# TSOL_102A.net
KiCad netlist of a schematic drawn in EAGLE
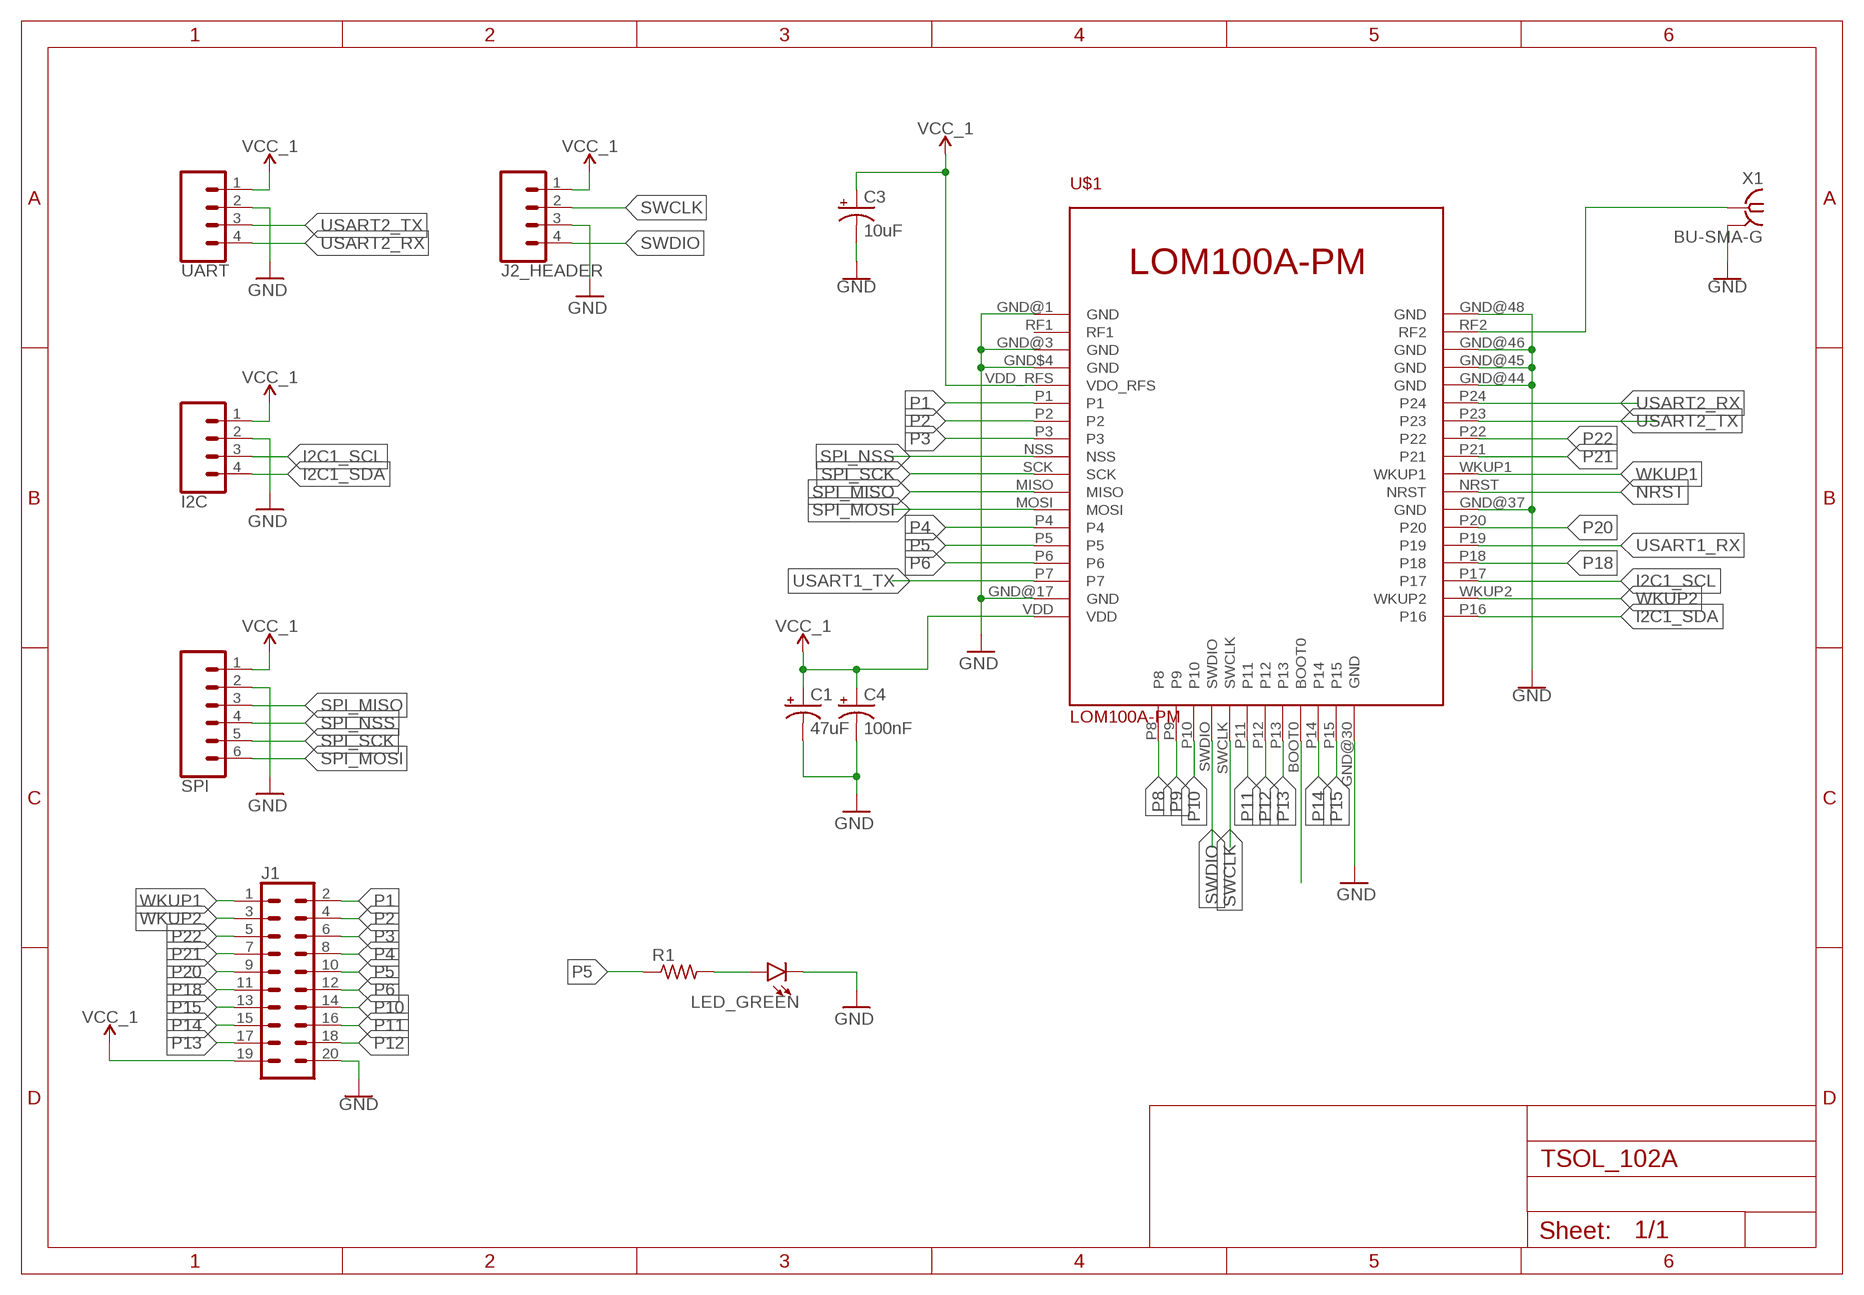
[diagram p0: schematic, sheet 1]

(export (version "E")
  (design (tool "Eeschema 10.0.6"))
  (components
    (comp (ref "C1")
      (value "47uF")
      (footprint "eagle-import:CPOL-RADIAL-5MM-10MM-KIT")
      (libsource (lib "eagle-import") (part "1000UF-RADIAL-5MM-35V-20%-KIT"))
    )
    (comp (ref "C3")
      (value "10uF")
      (footprint "eagle-import:CPOL-RADIAL-5MM-10MM-KIT")
      (libsource (lib "eagle-import") (part "1000UF-RADIAL-5MM-35V-20%-KIT"))
    )
    (comp (ref "C4")
      (value "100nF")
      (footprint "eagle-import:CPOL-RADIAL-5MM-10MM-KIT")
      (libsource (lib "eagle-import") (part "1000UF-RADIAL-5MM-35V-20%-KIT"))
    )
    (comp (ref "I2C")
      (value "CONN_04LONGPADS")
      (footprint "eagle-import:1X04_LONGPADS")
      (libsource (lib "eagle-import") (part "CONN_04LONGPADS"))
    )
    (comp (ref "J1")
      (value "CONN_10X2")
      (footprint "eagle-import:2X10")
      (libsource (lib "eagle-import") (part "CONN_10X2"))
    )
    (comp (ref "J2_HEADER")
      (value "CONN_04LONGPADS")
      (footprint "eagle-import:1X04_LONGPADS")
      (libsource (lib "eagle-import") (part "CONN_04LONGPADS"))
    )
    (comp (ref "LED_GREEN")
      (value "LED5MM")
      (footprint "eagle-import:LED_5MM")
      (libsource (lib "eagle-import") (part "LED5MM"))
    )
    (comp (ref "R1")
      (value "R-US_0204/7")
      (footprint "eagle-import:0204_7")
      (libsource (lib "eagle-import") (part "R-US_0204/7"))
    )
    (comp (ref "SPI")
      (value "CONN_06LONGPADS")
      (footprint "eagle-import:1X06_LONGPADS")
      (libsource (lib "eagle-import") (part "CONN_06LONGPADS"))
    )
    (comp (ref "U$1")
      (value "LOM100A-PM")
      (footprint "eagle-import:LOM100A-PM")
      (libsource (lib "eagle-import") (part "LOM100A-PM"))
    )
    (comp (ref "UART")
      (value "CONN_04LONGPADS")
      (footprint "eagle-import:1X04_LONGPADS")
      (libsource (lib "eagle-import") (part "CONN_04LONGPADS"))
    )
    (comp (ref "X1")
      (value "BU-SMA-G")
      (footprint "eagle-import:BU-SMA-G")
      (libsource (lib "eagle-import") (part "BU-SMA-G"))
    )
  )
  (nets
    (net (code "1") (name "GND") (class "Default")
      (node (ref "C1") (pin "-") (pinfunction "-_-") (pintype "passive"))
      (node (ref "C3") (pin "-") (pinfunction "-_-") (pintype "passive"))
      (node (ref "C4") (pin "-") (pinfunction "-_-") (pintype "passive"))
      (node (ref "I2C") (pin "2") (pinfunction "2_2") (pintype "passive"))
      (node (ref "J1") (pin "20") (pinfunction "20_20") (pintype "passive"))
      (node (ref "J2_HEADER") (pin "3") (pinfunction "3_3") (pintype "passive"))
      (node (ref "LED_GREEN") (pin "K") (pinfunction "C_K") (pintype "passive"))
      (node (ref "SPI") (pin "2") (pinfunction "2_2") (pintype "passive"))
      (node (ref "U$1") (pin "GND$4") (pinfunction "GND_GND$4") (pintype "passive"))
      (node (ref "U$1") (pin "GND@1") (pinfunction "GND_GND@1") (pintype "passive"))
      (node (ref "U$1") (pin "GND@17") (pinfunction "GND_GND@17") (pintype "passive"))
      (node (ref "U$1") (pin "GND@3") (pinfunction "GND_GND@3") (pintype "passive"))
      (node (ref "U$1") (pin "GND@30") (pinfunction "GND_GND@30") (pintype "passive"))
      (node (ref "U$1") (pin "GND@37") (pinfunction "GND_GND@37") (pintype "passive"))
      (node (ref "U$1") (pin "GND@44") (pinfunction "GND_GND@44") (pintype "passive"))
      (node (ref "U$1") (pin "GND@45") (pinfunction "GND_GND@45") (pintype "passive"))
      (node (ref "U$1") (pin "GND@46") (pinfunction "GND_GND@46") (pintype "passive"))
      (node (ref "U$1") (pin "GND@48") (pinfunction "GND_GND@48") (pintype "passive"))
      (node (ref "UART") (pin "2") (pinfunction "2_2") (pintype "passive"))
      (node (ref "X1") (pin "2") (pinfunction "2_2") (pintype "passive"))
      (node (ref "X1") (pin "3") (pinfunction "2_3") (pintype "passive"))
      (node (ref "X1") (pin "4") (pinfunction "2_4") (pintype "passive"))
      (node (ref "X1") (pin "5") (pinfunction "2_5") (pintype "passive"))
    )
    (net (code "2") (name "I2C1_SCL") (class "Default")
      (node (ref "I2C") (pin "3") (pinfunction "3_3") (pintype "passive"))
      (node (ref "U$1") (pin "P17") (pinfunction "P17_P17") (pintype "passive"))
    )
    (net (code "3") (name "I2C1_SDA") (class "Default")
      (node (ref "I2C") (pin "4") (pinfunction "4_4") (pintype "passive"))
      (node (ref "U$1") (pin "P16") (pinfunction "P16_P16") (pintype "passive"))
    )
    (net (code "4") (name "NRST") (class "Default")
      (node (ref "U$1") (pin "NRST") (pinfunction "NRST_NRST") (pintype "passive"))
    )
    (net (code "5") (name "Net-(LED_GREEN-PadA)") (class "Default")
      (node (ref "LED_GREEN") (pin "A") (pinfunction "A_A") (pintype "passive"))
      (node (ref "R1") (pin "2") (pinfunction "2_2") (pintype "passive"))
    )
    (net (code "6") (name "Net-(U$1-PadRF2)") (class "Default")
      (node (ref "U$1") (pin "RF2") (pinfunction "RF2_RF2") (pintype "passive"))
      (node (ref "X1") (pin "1") (pinfunction "1_1") (pintype "passive"))
    )
    (net (code "7") (name "P1") (class "Default")
      (node (ref "J1") (pin "2") (pinfunction "2_2") (pintype "passive"))
      (node (ref "U$1") (pin "P1") (pinfunction "P1_P1") (pintype "passive"))
    )
    (net (code "8") (name "P2") (class "Default")
      (node (ref "J1") (pin "4") (pinfunction "4_4") (pintype "passive"))
      (node (ref "U$1") (pin "P2") (pinfunction "P2_P2") (pintype "passive"))
    )
    (net (code "9") (name "P3") (class "Default")
      (node (ref "J1") (pin "6") (pinfunction "6_6") (pintype "passive"))
      (node (ref "U$1") (pin "P3") (pinfunction "P3_P3") (pintype "passive"))
    )
    (net (code "10") (name "P4") (class "Default")
      (node (ref "J1") (pin "8") (pinfunction "8_8") (pintype "passive"))
      (node (ref "U$1") (pin "P4") (pinfunction "P4_P4") (pintype "passive"))
    )
    (net (code "11") (name "P5") (class "Default")
      (node (ref "J1") (pin "10") (pinfunction "10_10") (pintype "passive"))
      (node (ref "R1") (pin "1") (pinfunction "1_1") (pintype "passive"))
      (node (ref "U$1") (pin "P5") (pinfunction "P5_P5") (pintype "passive"))
    )
    (net (code "12") (name "P6") (class "Default")
      (node (ref "J1") (pin "12") (pinfunction "12_12") (pintype "passive"))
      (node (ref "U$1") (pin "P6") (pinfunction "P6_P6") (pintype "passive"))
    )
    (net (code "13") (name "P8") (class "Default")
      (node (ref "U$1") (pin "P8") (pinfunction "P8_P8") (pintype "passive"))
    )
    (net (code "14") (name "P9") (class "Default")
      (node (ref "U$1") (pin "P9") (pinfunction "P9_P9") (pintype "passive"))
    )
    (net (code "15") (name "P10") (class "Default")
      (node (ref "J1") (pin "14") (pinfunction "14_14") (pintype "passive"))
      (node (ref "U$1") (pin "P10") (pinfunction "P10_P10") (pintype "passive"))
    )
    (net (code "16") (name "P11") (class "Default")
      (node (ref "J1") (pin "16") (pinfunction "16_16") (pintype "passive"))
      (node (ref "U$1") (pin "P11") (pinfunction "P11_P11") (pintype "passive"))
    )
    (net (code "17") (name "P12") (class "Default")
      (node (ref "J1") (pin "18") (pinfunction "18_18") (pintype "passive"))
      (node (ref "U$1") (pin "P12") (pinfunction "P12_P12") (pintype "passive"))
    )
    (net (code "18") (name "P13") (class "Default")
      (node (ref "J1") (pin "17") (pinfunction "17_17") (pintype "passive"))
      (node (ref "U$1") (pin "P13") (pinfunction "P13_P13") (pintype "passive"))
    )
    (net (code "19") (name "P14") (class "Default")
      (node (ref "J1") (pin "15") (pinfunction "15_15") (pintype "passive"))
      (node (ref "U$1") (pin "P14") (pinfunction "P14_P14") (pintype "passive"))
    )
    (net (code "20") (name "P15") (class "Default")
      (node (ref "J1") (pin "13") (pinfunction "13_13") (pintype "passive"))
      (node (ref "U$1") (pin "P15") (pinfunction "P15_P15") (pintype "passive"))
    )
    (net (code "21") (name "P18") (class "Default")
      (node (ref "J1") (pin "11") (pinfunction "11_11") (pintype "passive"))
      (node (ref "U$1") (pin "P18") (pinfunction "P18_P18") (pintype "passive"))
    )
    (net (code "22") (name "P20") (class "Default")
      (node (ref "J1") (pin "9") (pinfunction "9_9") (pintype "passive"))
      (node (ref "U$1") (pin "P20") (pinfunction "P20_P20") (pintype "passive"))
    )
    (net (code "23") (name "P21") (class "Default")
      (node (ref "J1") (pin "7") (pinfunction "7_7") (pintype "passive"))
      (node (ref "U$1") (pin "P21") (pinfunction "P21_P21") (pintype "passive"))
    )
    (net (code "24") (name "P22") (class "Default")
      (node (ref "J1") (pin "5") (pinfunction "5_5") (pintype "passive"))
      (node (ref "U$1") (pin "P22") (pinfunction "P22_P22") (pintype "passive"))
    )
    (net (code "25") (name "SPI_MISO") (class "Default")
      (node (ref "SPI") (pin "3") (pinfunction "3_3") (pintype "passive"))
      (node (ref "U$1") (pin "MISO") (pinfunction "MISO_MISO") (pintype "passive"))
    )
    (net (code "26") (name "SPI_MOSI") (class "Default")
      (node (ref "SPI") (pin "6") (pinfunction "6_6") (pintype "passive"))
      (node (ref "U$1") (pin "MOSI") (pinfunction "MOSI_MOSI") (pintype "passive"))
    )
    (net (code "27") (name "SPI_NSS") (class "Default")
      (node (ref "SPI") (pin "4") (pinfunction "4_4") (pintype "passive"))
      (node (ref "U$1") (pin "NSS") (pinfunction "NSS_NSS") (pintype "passive"))
    )
    (net (code "28") (name "SPI_SCK") (class "Default")
      (node (ref "SPI") (pin "5") (pinfunction "5_5") (pintype "passive"))
      (node (ref "U$1") (pin "SCK") (pinfunction "SCK_SCK") (pintype "passive"))
    )
    (net (code "29") (name "SWCLK") (class "Default")
      (node (ref "J2_HEADER") (pin "2") (pinfunction "2_2") (pintype "passive"))
      (node (ref "U$1") (pin "SWCLK") (pinfunction "SWCLK_SWCLK") (pintype "passive"))
    )
    (net (code "30") (name "SWDIO") (class "Default")
      (node (ref "J2_HEADER") (pin "4") (pinfunction "4_4") (pintype "passive"))
      (node (ref "U$1") (pin "SWDIO") (pinfunction "SWDIO_SWDIO") (pintype "passive"))
    )
    (net (code "31") (name "USART1_RX") (class "Default")
      (node (ref "U$1") (pin "P19") (pinfunction "P19_P19") (pintype "passive"))
    )
    (net (code "32") (name "USART1_TX") (class "Default")
      (node (ref "U$1") (pin "P7") (pinfunction "P7_P7") (pintype "passive"))
    )
    (net (code "33") (name "USART2_RX") (class "Default")
      (node (ref "U$1") (pin "P24") (pinfunction "P24_P24") (pintype "passive"))
      (node (ref "UART") (pin "4") (pinfunction "4_4") (pintype "passive"))
    )
    (net (code "34") (name "USART2_TX") (class "Default")
      (node (ref "U$1") (pin "P23") (pinfunction "P23_P23") (pintype "passive"))
      (node (ref "UART") (pin "3") (pinfunction "3_3") (pintype "passive"))
    )
    (net (code "35") (name "VCC_1") (class "Default")
      (node (ref "C1") (pin "+") (pinfunction "+_+") (pintype "passive"))
      (node (ref "C3") (pin "+") (pinfunction "+_+") (pintype "passive"))
      (node (ref "C4") (pin "+") (pinfunction "+_+") (pintype "passive"))
      (node (ref "I2C") (pin "1") (pinfunction "1_1") (pintype "passive"))
      (node (ref "J1") (pin "19") (pinfunction "19_19") (pintype "passive"))
      (node (ref "J2_HEADER") (pin "1") (pinfunction "1_1") (pintype "passive"))
      (node (ref "SPI") (pin "1") (pinfunction "1_1") (pintype "passive"))
      (node (ref "U$1") (pin "VDD") (pinfunction "VDD_VDD") (pintype "passive"))
      (node (ref "U$1") (pin "VDD_RFS") (pinfunction "VDO_RFS_VDD_RFS") (pintype "passive"))
      (node (ref "UART") (pin "1") (pinfunction "1_1") (pintype "passive"))
    )
    (net (code "36") (name "WKUP1") (class "Default")
      (node (ref "J1") (pin "1") (pinfunction "1_1") (pintype "passive"))
      (node (ref "U$1") (pin "WKUP1") (pinfunction "WKUP1_WKUP1") (pintype "passive"))
    )
    (net (code "37") (name "WKUP2") (class "Default")
      (node (ref "J1") (pin "3") (pinfunction "3_3") (pintype "passive"))
      (node (ref "U$1") (pin "WKUP2") (pinfunction "WKUP2_WKUP2") (pintype "passive"))
    )
    (net (code "38") (name "unconnected-(U$1-PadBOOT0)") (class "Default")
      (node (ref "U$1") (pin "BOOT0") (pinfunction "BOOT0_BOOT0") (pintype "passive"))
    )
    (net (code "39") (name "unconnected-(U$1-PadRF1)") (class "Default")
      (node (ref "U$1") (pin "RF1") (pinfunction "RF1_RF1") (pintype "passive"))
    )
  )
)
